# BMP388-Breakout_v10.net
KiCad netlist of a schematic drawn in EAGLE
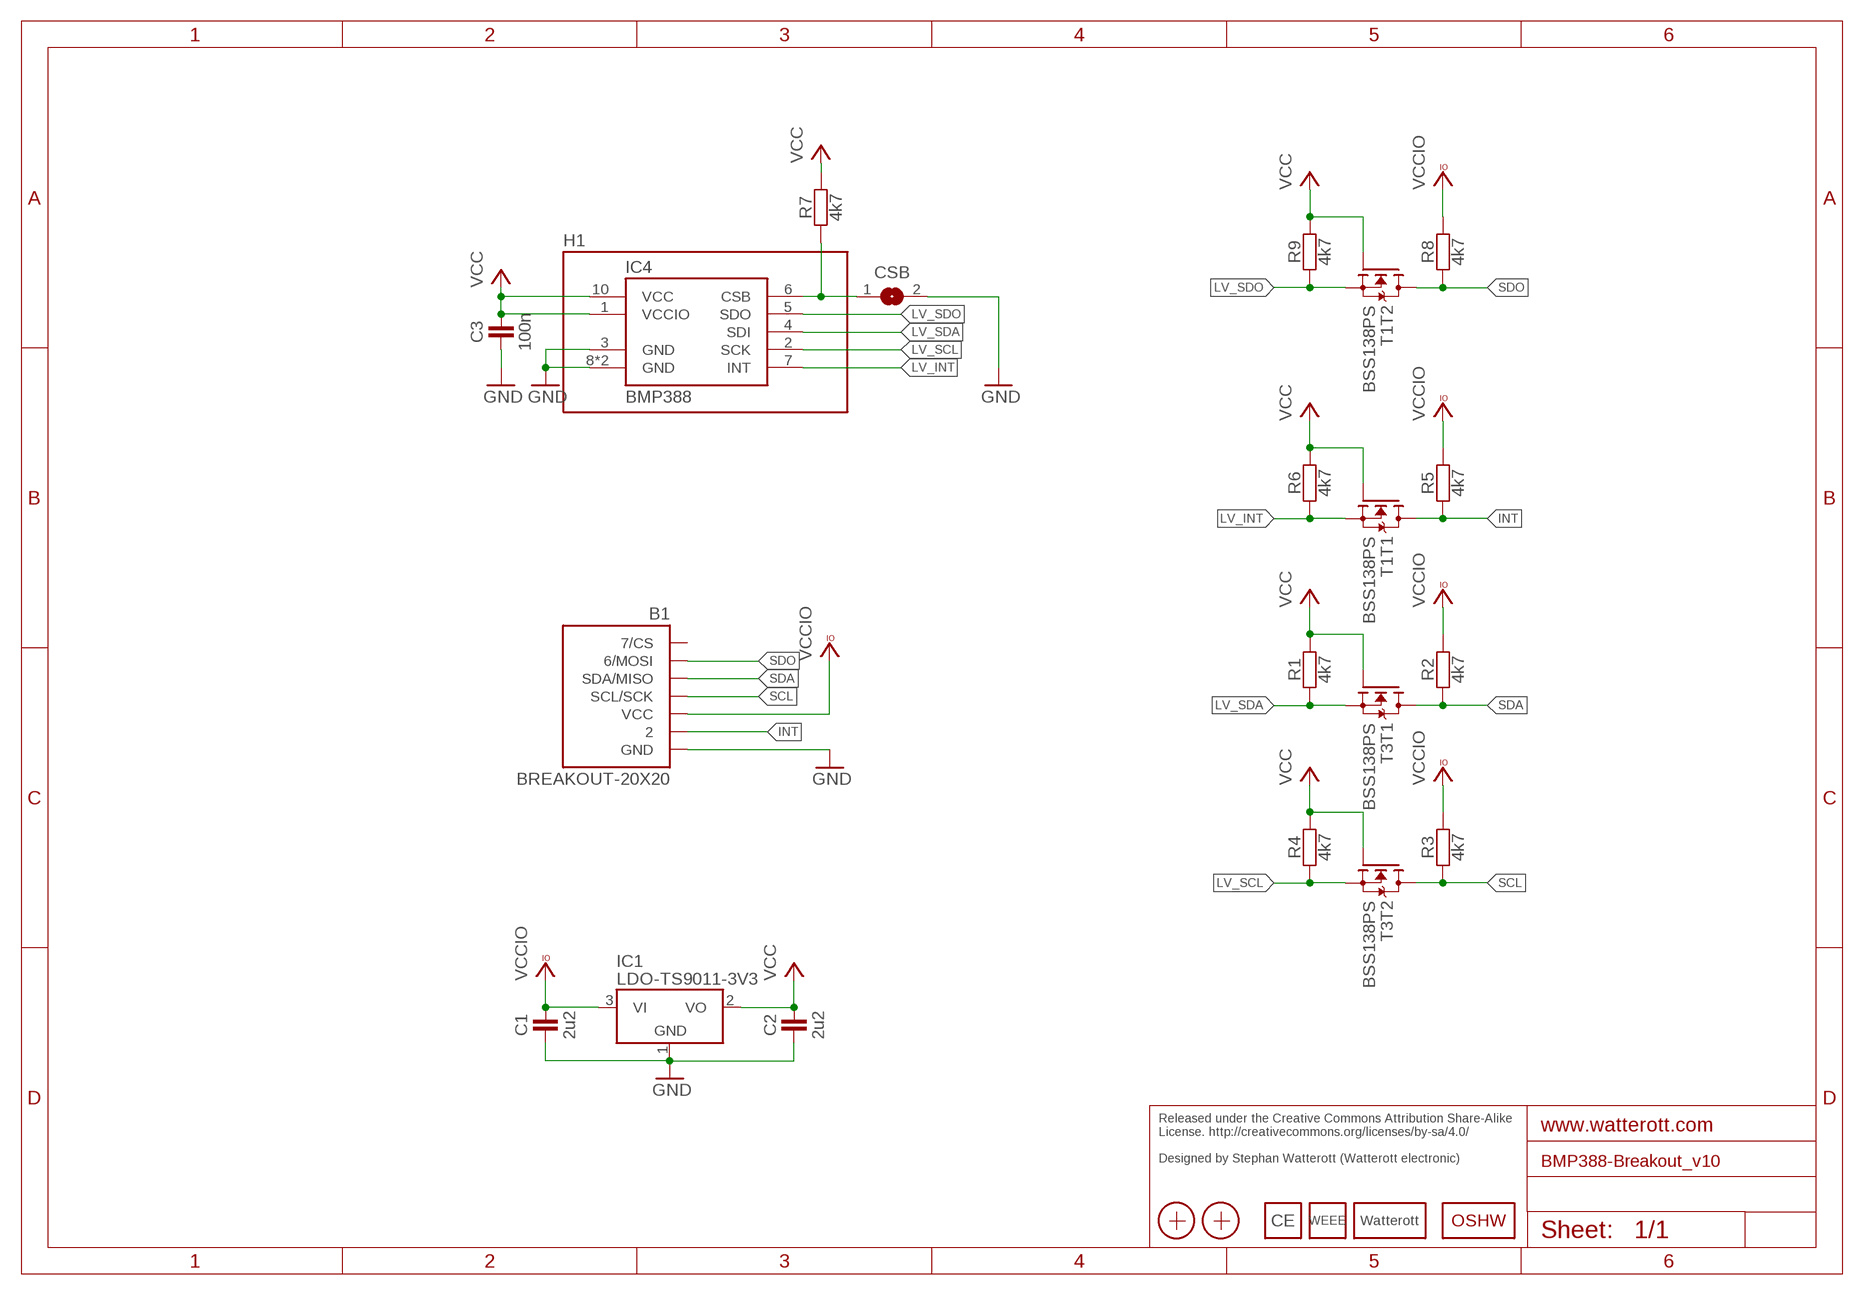
[diagram p0: schematic, sheet 1]

(export (version "E")
  (design (tool "Eeschema 10.0.6"))
  (components
    (comp (ref "B1")
      (value "BREAKOUT-20X20")
      (footprint "eagle-import:BREAKOUT-20X20")
      (libsource (lib "eagle-import") (part "BREAKOUT-20X20"))
    )
    (comp (ref "C1")
      (value "2u2")
      (footprint "eagle-import:C0402")
      (libsource (lib "eagle-import") (part "CAPACITOR-0402"))
    )
    (comp (ref "C2")
      (value "2u2")
      (footprint "eagle-import:C0402")
      (libsource (lib "eagle-import") (part "CAPACITOR-0402"))
    )
    (comp (ref "C3")
      (value "100n")
      (footprint "eagle-import:C0402")
      (libsource (lib "eagle-import") (part "CAPACITOR-0402"))
    )
    (comp (ref "CSB")
      (value "JUMPER2-0603-NC")
      (footprint "eagle-import:JUMPER2-0603_NC")
      (libsource (lib "eagle-import") (part "JUMPER2-0603-NC"))
    )
    (comp (ref "H1")
      (value "SF2")
      (footprint "eagle-import:SF2")
      (libsource (lib "eagle-import") (part "SF2"))
    )
    (comp (ref "IC1")
      (value "LDO-TS9011-3V3")
      (footprint "eagle-import:SOT23")
      (libsource (lib "eagle-import") (part "LDO-TS9011-3V3"))
    )
    (comp (ref "IC4")
      (value "BMP388")
      (footprint "eagle-import:BMP388")
      (libsource (lib "eagle-import") (part "BMP388"))
    )
    (comp (ref "LOGO2")
      (value "OSHW_LOGOX0070")
      (footprint "eagle-import:OSHW_6X70")
      (libsource (lib "eagle-import") (part "OSHW_LOGOX0070"))
    )
    (comp (ref "LOGO3")
      (value "LOGO_WEEE-4")
      (footprint "eagle-import:WEEE_4MM")
      (libsource (lib "eagle-import") (part "LOGO_WEEE-4"))
    )
    (comp (ref "LOGO4")
      (value "LOGO_CE-4")
      (footprint "eagle-import:CE_4MM")
      (libsource (lib "eagle-import") (part "LOGO_CE-4"))
    )
    (comp (ref "LOGO5")
      (value "LOGO_SPARK-4")
      (footprint "eagle-import:SPARK_4MM")
      (libsource (lib "eagle-import") (part "LOGO_SPARK-4"))
    )
    (comp (ref "R1")
      (value "4k7")
      (footprint "eagle-import:C0402")
      (libsource (lib "eagle-import") (part "RESISTOR-0402"))
    )
    (comp (ref "R2")
      (value "4k7")
      (footprint "eagle-import:C0402")
      (libsource (lib "eagle-import") (part "RESISTOR-0402"))
    )
    (comp (ref "R3")
      (value "4k7")
      (footprint "eagle-import:C0402")
      (libsource (lib "eagle-import") (part "RESISTOR-0402"))
    )
    (comp (ref "R4")
      (value "4k7")
      (footprint "eagle-import:C0402")
      (libsource (lib "eagle-import") (part "RESISTOR-0402"))
    )
    (comp (ref "R5")
      (value "4k7")
      (footprint "eagle-import:C0402")
      (libsource (lib "eagle-import") (part "RESISTOR-0402"))
    )
    (comp (ref "R6")
      (value "4k7")
      (footprint "eagle-import:C0402")
      (libsource (lib "eagle-import") (part "RESISTOR-0402"))
    )
    (comp (ref "R7")
      (value "4k7")
      (footprint "eagle-import:C0402")
      (libsource (lib "eagle-import") (part "RESISTOR-0402"))
    )
    (comp (ref "R8")
      (value "4k7")
      (footprint "eagle-import:C0402")
      (libsource (lib "eagle-import") (part "RESISTOR-0402"))
    )
    (comp (ref "R9")
      (value "4k7")
      (footprint "eagle-import:C0402")
      (libsource (lib "eagle-import") (part "RESISTOR-0402"))
    )
    (comp (ref "T1")
      (value "BSS138PS")
      (footprint "eagle-import:SOT363")
      (libsource (lib "eagle-import") (part "BSS138PS"))
    )
    (comp (ref "T3")
      (value "BSS138PS")
      (footprint "eagle-import:SOT363")
      (libsource (lib "eagle-import") (part "BSS138PS"))
    )
    (comp (ref "X1")
      (value "PASSER-07")
      (footprint "eagle-import:PASSER_07MM")
      (libsource (lib "eagle-import") (part "PASSER-07"))
    )
    (comp (ref "X2")
      (value "PASSER-07")
      (footprint "eagle-import:PASSER_07MM")
      (libsource (lib "eagle-import") (part "PASSER-07"))
    )
  )
  (nets
    (net (code "1") (name "GND") (class "Default")
      (node (ref "B1") (pin "GND") (pinfunction "GND_GND") (pintype "power_in"))
      (node (ref "C1") (pin "1") (pinfunction "1_1") (pintype "passive"))
      (node (ref "C2") (pin "1") (pinfunction "1_1") (pintype "passive"))
      (node (ref "C3") (pin "1") (pinfunction "1_1") (pintype "passive"))
      (node (ref "CSB") (pin "2") (pinfunction "2_2") (pintype "passive"))
      (node (ref "IC1") (pin "1") (pinfunction "GND_1") (pintype "passive"))
      (node (ref "IC4") (pin "3") (pinfunction "GND_3") (pintype "power_in"))
      (node (ref "IC4") (pin "8") (pinfunction "GND_8") (pintype "power_in"))
      (node (ref "IC4") (pin "9") (pinfunction "GND_9") (pintype "power_in"))
    )
    (net (code "2") (name "INT") (class "Default")
      (node (ref "B1") (pin "2") (pinfunction "2_2") (pintype "bidirectional"))
      (node (ref "R5") (pin "1") (pinfunction "1_1") (pintype "passive"))
      (node (ref "T1") (pin "6") (pinfunction "D_6") (pintype "passive"))
    )
    (net (code "3") (name "LV_INT") (class "Default")
      (node (ref "IC4") (pin "7") (pinfunction "INT_7") (pintype "bidirectional"))
      (node (ref "R6") (pin "1") (pinfunction "1_1") (pintype "passive"))
      (node (ref "T1") (pin "1") (pinfunction "S_1") (pintype "passive"))
    )
    (net (code "4") (name "LV_SCL") (class "Default")
      (node (ref "IC4") (pin "2") (pinfunction "SCK_2") (pintype "bidirectional"))
      (node (ref "R4") (pin "1") (pinfunction "1_1") (pintype "passive"))
      (node (ref "T3") (pin "4") (pinfunction "S_4") (pintype "passive"))
    )
    (net (code "5") (name "LV_SDA") (class "Default")
      (node (ref "IC4") (pin "4") (pinfunction "SDI_4") (pintype "bidirectional"))
      (node (ref "R1") (pin "1") (pinfunction "1_1") (pintype "passive"))
      (node (ref "T3") (pin "1") (pinfunction "S_1") (pintype "passive"))
    )
    (net (code "6") (name "LV_SDO") (class "Default")
      (node (ref "IC4") (pin "5") (pinfunction "SDO_5") (pintype "bidirectional"))
      (node (ref "R9") (pin "1") (pinfunction "1_1") (pintype "passive"))
      (node (ref "T1") (pin "4") (pinfunction "S_4") (pintype "passive"))
    )
    (net (code "7") (name "Net-(IC4-CSB)") (class "Default")
      (node (ref "CSB") (pin "1") (pinfunction "1_1") (pintype "passive"))
      (node (ref "IC4") (pin "6") (pinfunction "CSB_6") (pintype "input"))
      (node (ref "R7") (pin "1") (pinfunction "1_1") (pintype "passive"))
    )
    (net (code "8") (name "SCL") (class "Default")
      (node (ref "B1") (pin "SCL/SCK") (pinfunction "SCL/SCK_SCL/SCK") (pintype "bidirectional"))
      (node (ref "R3") (pin "1") (pinfunction "1_1") (pintype "passive"))
      (node (ref "T3") (pin "3") (pinfunction "D_3") (pintype "passive"))
    )
    (net (code "9") (name "SDA") (class "Default")
      (node (ref "B1") (pin "SDA/MISO") (pinfunction "SDA/MISO_SDA/MISO") (pintype "bidirectional"))
      (node (ref "R2") (pin "1") (pinfunction "1_1") (pintype "passive"))
      (node (ref "T3") (pin "6") (pinfunction "D_6") (pintype "passive"))
    )
    (net (code "10") (name "SDO") (class "Default")
      (node (ref "B1") (pin "MOSI") (pinfunction "6/MOSI_MOSI") (pintype "bidirectional"))
      (node (ref "R8") (pin "1") (pinfunction "1_1") (pintype "passive"))
      (node (ref "T1") (pin "3") (pinfunction "D_3") (pintype "passive"))
    )
    (net (code "11") (name "VCC") (class "Default")
      (node (ref "C2") (pin "2") (pinfunction "2_2") (pintype "passive"))
      (node (ref "C3") (pin "2") (pinfunction "2_2") (pintype "passive"))
      (node (ref "IC1") (pin "2") (pinfunction "VO_2") (pintype "passive"))
      (node (ref "IC4") (pin "1") (pinfunction "VCCIO_1") (pintype "power_in"))
      (node (ref "IC4") (pin "10") (pinfunction "VCC_10") (pintype "power_in"))
      (node (ref "R1") (pin "2") (pinfunction "2_2") (pintype "passive"))
      (node (ref "R4") (pin "2") (pinfunction "2_2") (pintype "passive"))
      (node (ref "R6") (pin "2") (pinfunction "2_2") (pintype "passive"))
      (node (ref "R7") (pin "2") (pinfunction "2_2") (pintype "passive"))
      (node (ref "R9") (pin "2") (pinfunction "2_2") (pintype "passive"))
      (node (ref "T1") (pin "2") (pinfunction "G_2") (pintype "passive"))
      (node (ref "T1") (pin "5") (pinfunction "G_5") (pintype "passive"))
      (node (ref "T3") (pin "2") (pinfunction "G_2") (pintype "passive"))
      (node (ref "T3") (pin "5") (pinfunction "G_5") (pintype "passive"))
    )
    (net (code "12") (name "VCCIO") (class "Default")
      (node (ref "B1") (pin "VCC") (pinfunction "VCC_VCC") (pintype "power_in"))
      (node (ref "C1") (pin "2") (pinfunction "2_2") (pintype "passive"))
      (node (ref "IC1") (pin "3") (pinfunction "VI_3") (pintype "input"))
      (node (ref "R2") (pin "2") (pinfunction "2_2") (pintype "passive"))
      (node (ref "R3") (pin "2") (pinfunction "2_2") (pintype "passive"))
      (node (ref "R5") (pin "2") (pinfunction "2_2") (pintype "passive"))
      (node (ref "R8") (pin "2") (pinfunction "2_2") (pintype "passive"))
    )
    (net (code "13") (name "unconnected-(B1-7{slash}CS-PadCS)") (class "Default")
      (node (ref "B1") (pin "CS") (pinfunction "7/CS_CS") (pintype "bidirectional"))
    )
  )
)
